# 30V_Output_Design.net
KiCad netlist of a schematic drawn in Altium Designer
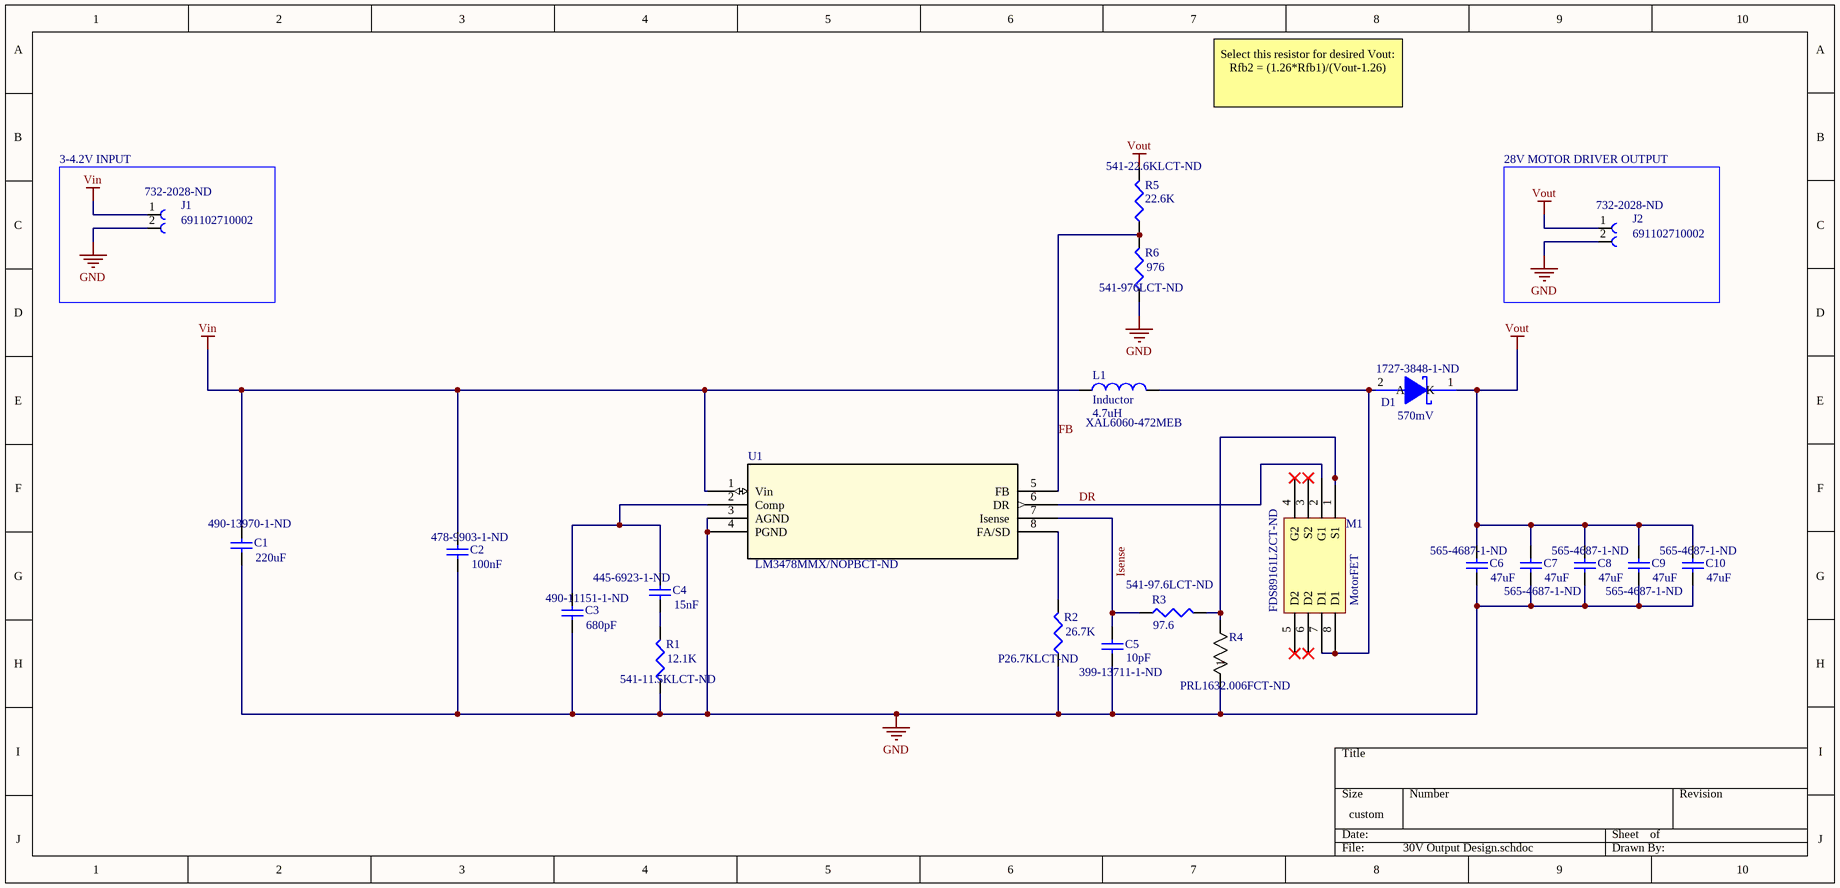
[diagram p0: 30V Output Design.schdoc]

(export (version "E")
  (design (tool "Eeschema 10.0.6"))
  (components
    (comp (ref "C1")
      (value "220uF")
      (footprint "C1206")
      (description "CAP CER 220UF 6.3V X5R 1210")
      (fields
        (field (name "SUPPLIER PART NUMBER 1") "490-13970-1-ND")
        (field (name "MANUFACTURER") "Murata")
        (field (name "MANUFACTURER PART NUMBER") "GRM31CR60J227ME11L")
        (field (name "PUBLISHER") "Altium Limited")
      )
      (libsource (lib "Miscellaneous Devices") (part "Cap Semi"))
    )
    (comp (ref "C2")
      (value "100nF")
      (footprint "1608[0603]")
      (fields
        (field (name "SUPPLIER PART NUMBER 1") "478-9903-1-ND")
        (field (name "Comment") "bypass cap")
        (field (name "PUBLISHER") "Altium Limited")
      )
      (libsource (lib "Miscellaneous Devices") (part "Cap Semi"))
    )
    (comp (ref "C3")
      (value "680pF")
      (footprint "0402")
      (description "CL05C681JB5NNNC - comparator cap 2")
      (fields
        (field (name "SUPPLIER PART NUMBER 1") "490-11151-1-ND")
        (field (name "Comment") "CL05C681JB5NNNC")
        (field (name "PUBLISHER") "Altium Limited")
      )
      (libsource (lib "Miscellaneous Devices") (part "Cap Semi"))
    )
    (comp (ref "C4")
      (value "15nF")
      (footprint "1608[0603]")
      (description "CGA4F2C0G1H153J085AA comparator cap")
      (fields
        (field (name "SUPPLIER PART NUMBER 1") "445-6923-1-ND")
        (field (name "Comment") "Cap Semi")
        (field (name "PUBLISHER") "Altium Limited")
      )
      (libsource (lib "Miscellaneous Devices") (part "Cap Semi"))
    )
    (comp (ref "C5")
      (value "10pF")
      (footprint "1608[0603]")
      (description "Capacitor (Semiconductor SIM Model) filter cap")
      (fields
        (field (name "SUPPLIER PART NUMBER 1") "399-13711-1-ND")
        (field (name "Comment") "CL21C100JBANNNC")
        (field (name "PUBLISHER") "Altium Limited")
      )
      (libsource (lib "Miscellaneous Devices") (part "Cap Semi"))
    )
    (comp (ref "C6")
      (value "47uF")
      (footprint "CAP-2 J-lead")
      (description "EEHZA1H101P - from TI output cap")
      (fields
        (field (name "SUPPLIER PART NUMBER 1") "565-4687-1-ND")
        (field (name "MANUFACTURER") "United Chemi-Con")
        (field (name "MANUFACTURER PART NUMBER") "KTJ500B476M76BFT00")
        (field (name "PUBLISHER") "Altium Limited")
      )
      (libsource (lib "Miscellaneous Devices") (part "Cap Semi"))
    )
    (comp (ref "C7")
      (value "47uF")
      (footprint "CAP-2 J-lead")
      (description "EEHZA1H101P - from TI output cap")
      (fields
        (field (name "SUPPLIER PART NUMBER 1") "565-4687-1-ND")
        (field (name "MANUFACTURER") "United Chemi-Con")
        (field (name "MANUFACTURER PART NUMBER") "KTJ500B476M76BFT00")
        (field (name "PUBLISHER") "Altium Limited")
      )
      (libsource (lib "Miscellaneous Devices") (part "Cap Semi"))
    )
    (comp (ref "C8")
      (value "47uF")
      (footprint "CAP-2 J-lead")
      (description "EEHZA1H101P - from TI output cap")
      (fields
        (field (name "SUPPLIER PART NUMBER 1") "565-4687-1-ND")
        (field (name "MANUFACTURER") "United Chemi-Con")
        (field (name "MANUFACTURER PART NUMBER") "KTJ500B476M76BFT00")
        (field (name "PUBLISHER") "Altium Limited")
      )
      (libsource (lib "Miscellaneous Devices") (part "Cap Semi"))
    )
    (comp (ref "C9")
      (value "47uF")
      (footprint "CAP-2 J-lead")
      (description "EEHZA1H101P - from TI output cap")
      (fields
        (field (name "SUPPLIER PART NUMBER 1") "565-4687-1-ND")
        (field (name "MANUFACTURER") "United Chemi-Con")
        (field (name "MANUFACTURER PART NUMBER") "KTJ500B476M76BFT00")
        (field (name "PUBLISHER") "Altium Limited")
      )
      (libsource (lib "Miscellaneous Devices") (part "Cap Semi"))
    )
    (comp (ref "C10")
      (value "47uF")
      (footprint "CAP-2 J-lead")
      (description "EEHZA1H101P - from TI output cap")
      (fields
        (field (name "SUPPLIER PART NUMBER 1") "565-4687-1-ND")
        (field (name "MANUFACTURER") "United Chemi-Con")
        (field (name "MANUFACTURER PART NUMBER") "KTJ500B476M76BFT00")
        (field (name "PUBLISHER") "Altium Limited")
      )
      (libsource (lib "Miscellaneous Devices") (part "Cap Semi"))
    )
    (comp (ref "D1")
      (value "570mV")
      (footprint "2019-05-27_23-32-10:SOD323F")
      (description "PMEG6010CEH,115")
      (fields
        (field (name "SUPPLIER PART NUMBER 1") "1727-3848-1-ND")
        (field (name "MANUFACTURER") "Nexperia")
      )
      (libsource (lib "TI WEBENCH") (part "D1"))
    )
    (comp (ref "J1")
      (value "691102710002")
      (footprint "CON2_SCREW_5.00MM_691102710002")
      (description "Screw terminal 0.33 mmÂ² Number of pins 2 Wuerth Elektronik Blue 1 pc_s_")
      (fields (field (name "MF") "Wurth Electronics") (field (name "SUPPLIER PART NUMBER 1") "732-2028-ND"))
      (libsource (lib "691102710002") (part "691102710002"))
    )
    (comp (ref "J2")
      (value "691102710002")
      (footprint "CON2_SCREW_5.00MM_691102710002")
      (description "Screw terminal 0.33 mmÂ² Number of pins 2 Wuerth Elektronik Blue 1 pc_s_")
      (fields (field (name "MF") "Wurth Electronics") (field (name "SUPPLIER PART NUMBER 1") "732-2028-ND"))
      (libsource (lib "691102710002") (part "691102710002"))
    )
    (comp (ref "L1")
      (value "Inductor")
      (footprint "XAL6060-472")
      (description "Inductor CoilCraft")
      (fields
        (field (name "ALTIUM_VALUE") "4.7uH")
        (field (name "SUPPLIER PART NUMBER 1") "XAL6060-472MEB")
        (field (name "MANUFACTURER") "Coilcraft")
        (field (name "MANUFACTURER PART NUMBER") "XAL6060-472MEB")
        (field (name "PUBLISHER") "Altium Limited")
      )
      (libsource (lib "Miscellaneous Devices") (part "Inductor"))
    )
    (comp (ref "M1")
      (value "MotorFET")
      (footprint "MotorFETSOIC127P590X175-8N")
      (fields
        (field (name "SUPPLIER PART NUMBER 1") "FDS89161LZCT-ND")
        (field (name "MANUFACTURER") "ON Semiconductor / Fairchild")
        (field (name "MANUFACTURER PART NUMBER") "FDS89161LZ")
      )
      (libsource (lib "ICs") (part "MotorFET"))
    )
    (comp (ref "R1")
      (value "12.1K")
      (footprint "RES_CRCW_0402")
      (description "comparator resistor")
      (fields
        (field (name "SUPPLIER PART NUMBER 1") "541-11.5KLCT-ND")
        (field (name "MANUFACTURER") "Vishay")
        (field (name "MANUFACTURER PART NUMBER") "CRCW040211K5FKED")
        (field (name "PUBLISHER") "Altium Limited")
      )
      (libsource (lib "Miscellaneous Devices") (part "Res3"))
    )
    (comp (ref "R2")
      (value "26.7K")
      (footprint "RES_CRCW_0402")
      (description "Resistor CRCW040226K7FKED 0402")
      (fields
        (field (name "SUPPLIER PART NUMBER 1") "P26.7KLCT-ND")
        (field (name "MANUFACTURER") "Panasonic")
        (field (name "MANUFACTURER PART NUMBER") "ERJ-2RKF2672X")
      )
      (libsource (lib "Miscellaneous Devices") (part "Res3"))
    )
    (comp (ref "R3")
      (value "97.6")
      (footprint "RES_CRCW_0402")
      (description "Resistor CRCW040297R6FKED 0402")
      (fields
        (field (name "SUPPLIER PART NUMBER 1") "541-97.6LCT-ND")
        (field (name "MANUFACTURER") "Vishay")
        (field (name "MANUFACTURER PART NUMBER") "CRCW040297R6FKED")
        (field (name "PUBLISHER") "Altium Limited")
      )
      (libsource (lib "Miscellaneous Devices") (part "Res3"))
    )
    (comp (ref "R4")
      (value "PRL1632-R006-F-T1")
      (footprint "RES_3216")
      (description "No Description Available")
      (fields
        (field (name "SUPPLIER PART NUMBER 1") "PRL1632.006FCT-ND")
        (field (name "MANUFACTURER") "Susumu")
        (field (name "TOLERANCE") "1%")
        (field (name "COPYRIGHT") "Copyright (C) 2018 Accelerated Designs. All rights reserved")
      )
      (libsource (lib "2019-06-03_23-23-21") (part "PRL1632-R006-F-T"))
    )
    (comp (ref "R5")
      (value "22.6K")
      (footprint "RES_CRCW_0402")
      (description "Resistor CRCW040222K6FKED 0402")
      (fields
        (field (name "SUPPLIER PART NUMBER 1") "541-22.6KLCT-ND")
        (field (name "MANUFACTURER") "Vishay")
        (field (name "MANUFACTURER PART NUMBER") "CRCW040222K6FKED")
        (field (name "PUBLISHER") "Altium Limited")
      )
      (libsource (lib "Miscellaneous Devices") (part "Res3"))
    )
    (comp (ref "R6")
      (value "976")
      (footprint "RES_CRCW_0402")
      (description "Resistor CRCW0402976RFKED 0402")
      (fields
        (field (name "SUPPLIER PART NUMBER 1") "541-976LCT-ND")
        (field (name "MANUFACTURER") "Vishay")
        (field (name "MANUFACTURER PART NUMBER") "CRCW0402976RFKED")
        (field (name "PUBLISHER") "Altium Limited")
      )
      (libsource (lib "Miscellaneous Devices") (part "Res3"))
    )
    (comp (ref "U1")
      (value "Part Number: LM3478MMX/NOPB")
      (footprint "MUA08A")
      (description "No Description Available")
      (fields
        (field (name "MANUFACTURER_PART_NUMBER") "LM3478MMX/NOPB")
        (field (name "SUPPLIER PART NUMBER 1") "LM3478MMX/NOPBCT-ND")
        (field (name "MANUFACTURER") "TI National Semiconductor")
        (field (name "COPYRIGHT") "Copyright (C) 2018 Accelerated Designs. All rights reserved")
      )
      (libsource (lib "2019-05-29_05-12-58") (part "LM3478MMX/NOPB"))
    )
  )
  (nets
    (net (code "1") (name "/DR") (class "Default")
      (node (ref "M1") (pin "2") (pinfunction "G1_2") (pintype "passive"))
      (node (ref "U1") (pin "6") (pinfunction "DR_6") (pintype "output"))
    )
    (net (code "2") (name "/FB") (class "Default")
      (node (ref "R5") (pin "1") (pinfunction "1_1") (pintype "passive"))
      (node (ref "R6") (pin "2") (pinfunction "2_2") (pintype "passive"))
      (node (ref "U1") (pin "5") (pinfunction "FB_5") (pintype "passive"))
    )
    (net (code "3") (name "/Isense") (class "Default")
      (node (ref "C5") (pin "2") (pinfunction "2_2") (pintype "passive"))
      (node (ref "R3") (pin "1") (pinfunction "1_1") (pintype "passive"))
      (node (ref "U1") (pin "7") (pinfunction "Isense_7") (pintype "passive"))
    )
    (net (code "4") (name "GND") (class "Default")
      (node (ref "C1") (pin "1") (pinfunction "1_1") (pintype "passive"))
      (node (ref "C10") (pin "1") (pinfunction "1_1") (pintype "passive"))
      (node (ref "C2") (pin "1") (pinfunction "1_1") (pintype "passive"))
      (node (ref "C3") (pin "1") (pinfunction "1_1") (pintype "passive"))
      (node (ref "C5") (pin "1") (pinfunction "1_1") (pintype "passive"))
      (node (ref "C6") (pin "1") (pinfunction "1_1") (pintype "passive"))
      (node (ref "C7") (pin "1") (pinfunction "1_1") (pintype "passive"))
      (node (ref "C8") (pin "1") (pinfunction "1_1") (pintype "passive"))
      (node (ref "C9") (pin "1") (pinfunction "1_1") (pintype "passive"))
      (node (ref "J1") (pin "2") (pinfunction "2_2") (pintype "passive"))
      (node (ref "J2") (pin "2") (pinfunction "2_2") (pintype "passive"))
      (node (ref "R1") (pin "1") (pinfunction "1_1") (pintype "passive"))
      (node (ref "R2") (pin "1") (pinfunction "1_1") (pintype "passive"))
      (node (ref "R4") (pin "1") (pinfunction "1_1") (pintype "passive"))
      (node (ref "R6") (pin "1") (pinfunction "1_1") (pintype "passive"))
      (node (ref "U1") (pin "3") (pinfunction "AGND_3") (pintype "power_in"))
      (node (ref "U1") (pin "4") (pinfunction "PGND_4") (pintype "power_in"))
    )
    (net (code "5") (name "Net-(C4-Pad1)") (class "Default")
      (node (ref "C4") (pin "1") (pinfunction "1_1") (pintype "passive"))
      (node (ref "R1") (pin "2") (pinfunction "2_2") (pintype "passive"))
    )
    (net (code "6") (name "Net-(D1-A)") (class "Default")
      (node (ref "D1") (pin "2") (pinfunction "A_2") (pintype "passive"))
      (node (ref "L1") (pin "2") (pinfunction "2_2") (pintype "passive"))
      (node (ref "M1") (pin "7") (pinfunction "D1_7") (pintype "passive"))
      (node (ref "M1") (pin "8") (pinfunction "D1_8") (pintype "passive"))
    )
    (net (code "7") (name "Net-(M1-S1)") (class "Default")
      (node (ref "M1") (pin "1") (pinfunction "S1_1") (pintype "passive"))
      (node (ref "R3") (pin "2") (pinfunction "2_2") (pintype "passive"))
      (node (ref "R4") (pin "2") (pinfunction "2_2") (pintype "passive"))
    )
    (net (code "8") (name "Net-(U1-Comp)") (class "Default")
      (node (ref "C3") (pin "2") (pinfunction "2_2") (pintype "passive"))
      (node (ref "C4") (pin "2") (pinfunction "2_2") (pintype "passive"))
      (node (ref "U1") (pin "2") (pinfunction "Comp_2") (pintype "passive"))
    )
    (net (code "9") (name "Net-(U1-FA{slash}SD)") (class "Default")
      (node (ref "R2") (pin "2") (pinfunction "2_2") (pintype "passive"))
      (node (ref "U1") (pin "8") (pinfunction "FA/SD_8") (pintype "passive"))
    )
    (net (code "10") (name "Vin") (class "Default")
      (node (ref "C1") (pin "2") (pinfunction "2_2") (pintype "passive"))
      (node (ref "C2") (pin "2") (pinfunction "2_2") (pintype "passive"))
      (node (ref "J1") (pin "1") (pinfunction "1_1") (pintype "passive"))
      (node (ref "L1") (pin "1") (pinfunction "1_1") (pintype "passive"))
      (node (ref "U1") (pin "1") (pinfunction "Vin_1") (pintype "bidirectional"))
    )
    (net (code "11") (name "Vout") (class "Default")
      (node (ref "C10") (pin "2") (pinfunction "2_2") (pintype "passive"))
      (node (ref "C6") (pin "2") (pinfunction "2_2") (pintype "passive"))
      (node (ref "C7") (pin "2") (pinfunction "2_2") (pintype "passive"))
      (node (ref "C8") (pin "2") (pinfunction "2_2") (pintype "passive"))
      (node (ref "C9") (pin "2") (pinfunction "2_2") (pintype "passive"))
      (node (ref "D1") (pin "1") (pinfunction "K_1") (pintype "passive"))
      (node (ref "J2") (pin "1") (pinfunction "1_1") (pintype "passive"))
      (node (ref "R5") (pin "2") (pinfunction "2_2") (pintype "passive"))
    )
    (net (code "12") (name "unconnected-(M1-D2-Pad5)") (class "Default")
      (node (ref "M1") (pin "5") (pinfunction "D2_5") (pintype "passive+no_connect"))
    )
    (net (code "13") (name "unconnected-(M1-D2-Pad6)") (class "Default")
      (node (ref "M1") (pin "6") (pinfunction "D2_6") (pintype "passive+no_connect"))
    )
    (net (code "14") (name "unconnected-(M1-G2-Pad4)") (class "Default")
      (node (ref "M1") (pin "4") (pinfunction "G2_4") (pintype "passive+no_connect"))
    )
    (net (code "15") (name "unconnected-(M1-S2-Pad3)") (class "Default")
      (node (ref "M1") (pin "3") (pinfunction "S2_3") (pintype "passive+no_connect"))
    )
  )
)
